# Gateway.net
KiCad netlist of a schematic drawn in Altium Designer
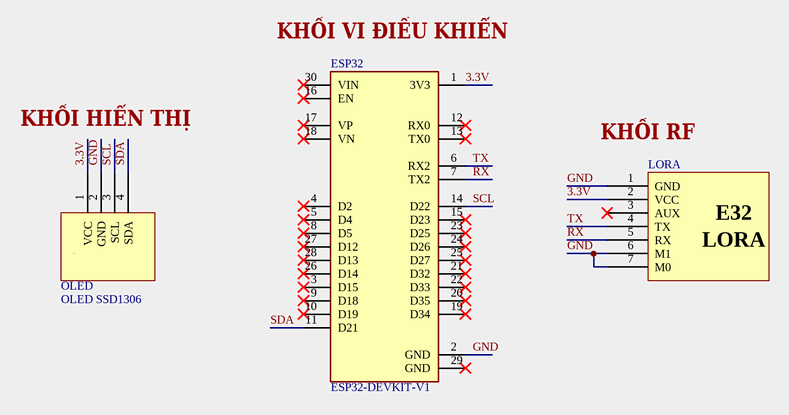
[diagram p0: Gateway.SchDoc]

(export (version "E")
  (design (tool "Eeschema 10.0.6"))
  (components
    (comp (ref "ESP32")
      (value "ESP32-DEVKIT-V1")
      (footprint "MODULE_ESP32_DEVKIT_V1")
      (fields (field (name "MF") "Do it"))
      (libsource (lib "Symbol") (part "ESP32-DEVKIT-V1"))
    )
    (comp (ref "LORA")
      (value "~")
      (footprint "LORA-E32")
      (description "Design By @Alixahedi")
      (libsource (lib "Symbol") (part "LORA-E32"))
    )
    (comp (ref "OLED")
      (value "OLED SSD1306")
      (footprint "SSD1306")
      (libsource (lib "Symbol") (part "SSD1306"))
    )
  )
  (nets
    (net (code "1") (name "/3.3V") (class "Default")
      (node (ref "ESP32") (pin "1") (pinfunction "3V3_1") (pintype "passive"))
      (node (ref "LORA") (pin "2") (pinfunction "VCC_2") (pintype "passive"))
      (node (ref "OLED") (pin "1") (pinfunction "VCC_1") (pintype "passive"))
    )
    (net (code "2") (name "/GND") (class "Default")
      (node (ref "ESP32") (pin "2") (pinfunction "GND_2") (pintype "passive"))
      (node (ref "LORA") (pin "1") (pinfunction "GND_1") (pintype "passive"))
      (node (ref "LORA") (pin "6") (pinfunction "M1_6") (pintype "passive"))
      (node (ref "LORA") (pin "7") (pinfunction "M0_7") (pintype "passive"))
      (node (ref "OLED") (pin "2") (pinfunction "GND_2") (pintype "passive"))
    )
    (net (code "3") (name "/RX") (class "Default")
      (node (ref "ESP32") (pin "7") (pinfunction "TX2_7") (pintype "passive"))
      (node (ref "LORA") (pin "5") (pinfunction "RX_5") (pintype "passive"))
    )
    (net (code "4") (name "/SCL") (class "Default")
      (node (ref "ESP32") (pin "14") (pinfunction "D22_14") (pintype "passive"))
      (node (ref "OLED") (pin "3") (pinfunction "SCL_3") (pintype "passive"))
    )
    (net (code "5") (name "/SDA") (class "Default")
      (node (ref "ESP32") (pin "11") (pinfunction "D21_11") (pintype "passive"))
      (node (ref "OLED") (pin "4") (pinfunction "SDA_4") (pintype "passive"))
    )
    (net (code "6") (name "/TX") (class "Default")
      (node (ref "ESP32") (pin "6") (pinfunction "RX2_6") (pintype "passive"))
      (node (ref "LORA") (pin "4") (pinfunction "TX_4") (pintype "passive"))
    )
    (net (code "7") (name "unconnected-(ESP32-D2-Pad4)") (class "Default")
      (node (ref "ESP32") (pin "4") (pinfunction "D2_4") (pintype "passive+no_connect"))
    )
    (net (code "8") (name "unconnected-(ESP32-D4-Pad5)") (class "Default")
      (node (ref "ESP32") (pin "5") (pinfunction "D4_5") (pintype "passive+no_connect"))
    )
    (net (code "9") (name "unconnected-(ESP32-D5-Pad8)") (class "Default")
      (node (ref "ESP32") (pin "8") (pinfunction "D5_8") (pintype "passive+no_connect"))
    )
    (net (code "10") (name "unconnected-(ESP32-D12-Pad27)") (class "Default")
      (node (ref "ESP32") (pin "27") (pinfunction "D12_27") (pintype "passive+no_connect"))
    )
    (net (code "11") (name "unconnected-(ESP32-D13-Pad28)") (class "Default")
      (node (ref "ESP32") (pin "28") (pinfunction "D13_28") (pintype "passive+no_connect"))
    )
    (net (code "12") (name "unconnected-(ESP32-D14-Pad26)") (class "Default")
      (node (ref "ESP32") (pin "26") (pinfunction "D14_26") (pintype "passive+no_connect"))
    )
    (net (code "13") (name "unconnected-(ESP32-D15-Pad3)") (class "Default")
      (node (ref "ESP32") (pin "3") (pinfunction "D15_3") (pintype "passive+no_connect"))
    )
    (net (code "14") (name "unconnected-(ESP32-D18-Pad9)") (class "Default")
      (node (ref "ESP32") (pin "9") (pinfunction "D18_9") (pintype "passive+no_connect"))
    )
    (net (code "15") (name "unconnected-(ESP32-D19-Pad10)") (class "Default")
      (node (ref "ESP32") (pin "10") (pinfunction "D19_10") (pintype "passive+no_connect"))
    )
    (net (code "16") (name "unconnected-(ESP32-D23-Pad15)") (class "Default")
      (node (ref "ESP32") (pin "15") (pinfunction "D23_15") (pintype "passive+no_connect"))
    )
    (net (code "17") (name "unconnected-(ESP32-D25-Pad23)") (class "Default")
      (node (ref "ESP32") (pin "23") (pinfunction "D25_23") (pintype "passive+no_connect"))
    )
    (net (code "18") (name "unconnected-(ESP32-D26-Pad24)") (class "Default")
      (node (ref "ESP32") (pin "24") (pinfunction "D26_24") (pintype "passive+no_connect"))
    )
    (net (code "19") (name "unconnected-(ESP32-D27-Pad25)") (class "Default")
      (node (ref "ESP32") (pin "25") (pinfunction "D27_25") (pintype "passive+no_connect"))
    )
    (net (code "20") (name "unconnected-(ESP32-D32-Pad21)") (class "Default")
      (node (ref "ESP32") (pin "21") (pinfunction "D32_21") (pintype "passive+no_connect"))
    )
    (net (code "21") (name "unconnected-(ESP32-D33-Pad22)") (class "Default")
      (node (ref "ESP32") (pin "22") (pinfunction "D33_22") (pintype "passive+no_connect"))
    )
    (net (code "22") (name "unconnected-(ESP32-D34-Pad19)") (class "Default")
      (node (ref "ESP32") (pin "19") (pinfunction "D34_19") (pintype "passive+no_connect"))
    )
    (net (code "23") (name "unconnected-(ESP32-D35-Pad20)") (class "Default")
      (node (ref "ESP32") (pin "20") (pinfunction "D35_20") (pintype "passive+no_connect"))
    )
    (net (code "24") (name "unconnected-(ESP32-EN-Pad16)") (class "Default")
      (node (ref "ESP32") (pin "16") (pinfunction "EN_16") (pintype "passive+no_connect"))
    )
    (net (code "25") (name "unconnected-(ESP32-GND-Pad29)") (class "Default")
      (node (ref "ESP32") (pin "29") (pinfunction "GND_29") (pintype "passive+no_connect"))
    )
    (net (code "26") (name "unconnected-(ESP32-RX0-Pad12)") (class "Default")
      (node (ref "ESP32") (pin "12") (pinfunction "RX0_12") (pintype "passive+no_connect"))
    )
    (net (code "27") (name "unconnected-(ESP32-TX0-Pad13)") (class "Default")
      (node (ref "ESP32") (pin "13") (pinfunction "TX0_13") (pintype "passive+no_connect"))
    )
    (net (code "28") (name "unconnected-(ESP32-VIN-Pad30)") (class "Default")
      (node (ref "ESP32") (pin "30") (pinfunction "VIN_30") (pintype "passive+no_connect"))
    )
    (net (code "29") (name "unconnected-(ESP32-VN-Pad18)") (class "Default")
      (node (ref "ESP32") (pin "18") (pinfunction "VN_18") (pintype "passive+no_connect"))
    )
    (net (code "30") (name "unconnected-(ESP32-VP-Pad17)") (class "Default")
      (node (ref "ESP32") (pin "17") (pinfunction "VP_17") (pintype "passive+no_connect"))
    )
    (net (code "31") (name "unconnected-(LORA-AUX-Pad3)") (class "Default")
      (node (ref "LORA") (pin "3") (pinfunction "AUX_3") (pintype "passive+no_connect"))
    )
  )
)
